# Sheet2.net
KiCad netlist of a schematic drawn in Altium Designer
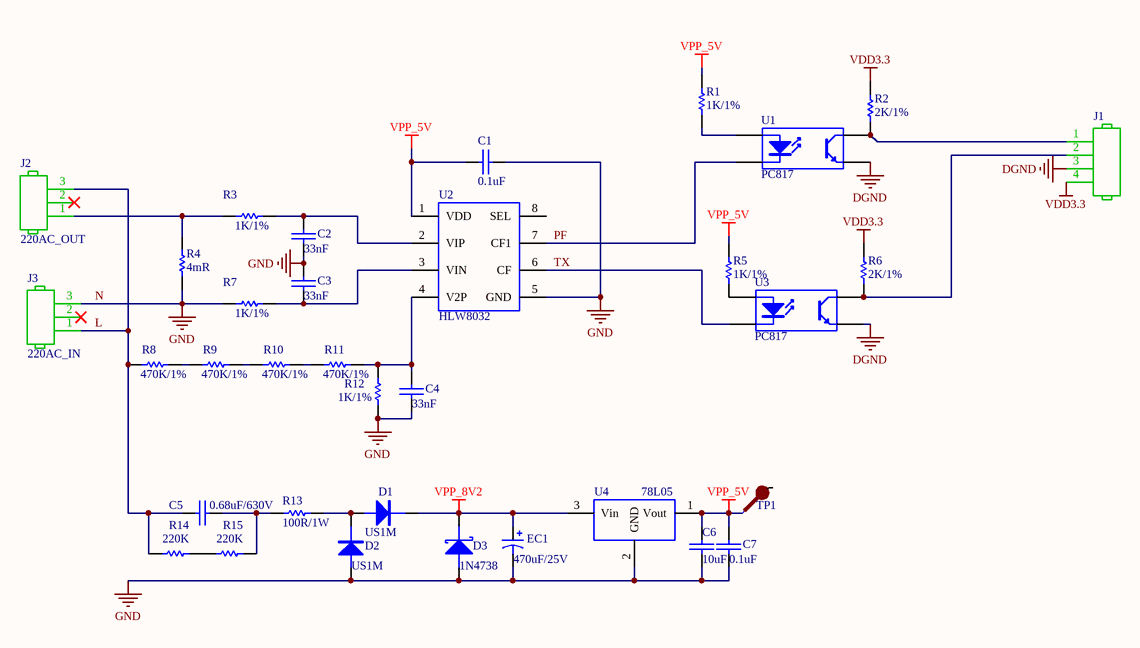
[diagram p0: Sheet2.SchDoc]

(export (version "E")
  (design (tool "Eeschema 10.0.6"))
  (components
    (comp (ref "C1")
      (value "0.1uF")
      (footprint "C0805")
      (description "33nF/50V/±10%/X7R")
      (libsource (lib "MYSchlib") (part "CAP"))
    )
    (comp (ref "C2")
      (value "33nF")
      (footprint "C0805")
      (description "33nF/50V/±10%/X7R")
      (libsource (lib "MYSchlib") (part "CAP"))
    )
    (comp (ref "C3")
      (value "33nF")
      (footprint "C0805")
      (description "33nF/50V/±10%/X7R")
      (libsource (lib "MYSchlib") (part "CAP"))
    )
    (comp (ref "C4")
      (value "33nF")
      (footprint "C0805")
      (description "33nF/50V/±10%/X7R")
      (libsource (lib "MYSchlib") (part "CAP"))
    )
    (comp (ref "C5")
      (value "0.68uF/630V")
      (footprint "CBB-20-V")
      (description "0.68uF/630V/CBB电容/脚距20")
      (libsource (lib "MYSchlib") (part "CAP"))
    )
    (comp (ref "C6")
      (value "10uF")
      (footprint "C0805")
      (description "10uF/10V/±10%/X7R")
      (libsource (lib "AD-SchLibV0.1-20160831") (part "CAP"))
    )
    (comp (ref "C7")
      (value "0.1uF")
      (footprint "C0805")
      (description "0.1uF/50V/±10%/X7R")
      (libsource (lib "MYSchlib") (part "CAP"))
    )
    (comp (ref "D1") (value "US1M") (footprint "DO-214AC(SMA)") (libsource (lib "MYSchlib") (part "DIODE")))
    (comp (ref "D2") (value "US1M") (footprint "DO-214AC(SMA)") (libsource (lib "MYSchlib") (part "DIODE")))
    (comp (ref "D3")
      (value "1N4738")
      (footprint "DO-214AC(SMA)")
      (libsource (lib "MYSchlib") (part "DIODE-S"))
    )
    (comp (ref "EC1")
      (value "470uF/25V")
      (footprint "C-IP-D8")
      (description "470uF/25V/±20%/8*12")
      (libsource (lib "MYSchlib") (part "CAP3"))
    )
    (comp (ref "J1")
      (value "~")
      (footprint "J-XH2.54-4-IPV")
      (description "XH2.54_4PIN/直插立式")
      (libsource (lib "my") (part "Header4"))
    )
    (comp (ref "J2")
      (value "220AC_OUT")
      (footprint "J-VH3.96-3-IPV")
      (description "VH3.96-3PIN/2脚空置/直插立式")
      (libsource (lib "my") (part "Header3"))
    )
    (comp (ref "J3")
      (value "220AC_IN")
      (footprint "J-VH3.96-3-IPV")
      (description "VH3.96-3PIN/2脚空置/直插立式")
      (libsource (lib "my") (part "Header3"))
    )
    (comp (ref "R1")
      (value "1K/1%")
      (footprint "R0805")
      (description "1K/±5%/1/10W")
      (libsource (lib "MYSchlib") (part "RES1"))
    )
    (comp (ref "R2")
      (value "2K/1%")
      (footprint "R0805")
      (description "1K/±5%/1/10W")
      (libsource (lib "MYSchlib") (part "RES1"))
    )
    (comp (ref "R3")
      (value "1K/1%")
      (footprint "R0805")
      (description "1K/±5%/1/10W")
      (libsource (lib "MYSchlib") (part "RES1"))
    )
    (comp (ref "R4")
      (value "4mR")
      (footprint "R-2512")
      (description "220K/±5%/1/4W")
      (libsource (lib "MYSchlib") (part "RES1"))
    )
    (comp (ref "R5")
      (value "1K/1%")
      (footprint "R0805")
      (description "1K/±5%/1/10W")
      (libsource (lib "MYSchlib") (part "RES1"))
    )
    (comp (ref "R6")
      (value "2K/1%")
      (footprint "R0805")
      (description "1K/±5%/1/10W")
      (libsource (lib "MYSchlib") (part "RES1"))
    )
    (comp (ref "R7")
      (value "1K/1%")
      (footprint "R0805")
      (description "1K/±5%/1/10W")
      (libsource (lib "MYSchlib") (part "RES1"))
    )
    (comp (ref "R8")
      (value "470K/1%")
      (footprint "R0805")
      (description "1K/±5%/1/10W")
      (libsource (lib "MYSchlib") (part "RES1"))
    )
    (comp (ref "R9")
      (value "470K/1%")
      (footprint "R0805")
      (description "1K/±5%/1/10W")
      (libsource (lib "MYSchlib") (part "RES1"))
    )
    (comp (ref "R10")
      (value "470K/1%")
      (footprint "R0805")
      (description "1K/±5%/1/10W")
      (libsource (lib "MYSchlib") (part "RES1"))
    )
    (comp (ref "R11")
      (value "470K/1%")
      (footprint "R0805")
      (description "1K/±5%/1/10W")
      (libsource (lib "MYSchlib") (part "RES1"))
    )
    (comp (ref "R12")
      (value "1K/1%")
      (footprint "R0805")
      (description "1K/±5%/1/10W")
      (libsource (lib "MYSchlib") (part "RES1"))
    )
    (comp (ref "R13")
      (value "100R/1W")
      (footprint "R-2512")
      (description "100R/±5%/1W/绕线电阻")
      (libsource (lib "MYSchlib") (part "RES1"))
    )
    (comp (ref "R14")
      (value "220K")
      (footprint "R-1206")
      (description "220K/±5%/1/4W")
      (libsource (lib "MYSchlib") (part "RES1"))
    )
    (comp (ref "R15")
      (value "220K")
      (footprint "R-1206")
      (description "220K/±5%/1/4W")
      (libsource (lib "MYSchlib") (part "RES1"))
    )
    (comp (ref "TP1") (value "TEST POINT") (footprint "TP-D2") (libsource (lib "MYSchlib") (part "TEST")))
    (comp (ref "U1")
      (value "PC817")
      (footprint "SOP4-2.54-6.5")
      (description "PC817C")
      (libsource (lib "MYSchlib") (part "PC817"))
    )
    (comp (ref "U2")
      (value "HLW8032")
      (footprint "SOP8-1.27-3.9")
      (description "HLW8012")
      (libsource (lib "MYSchlib") (part "HLW8012"))
    )
    (comp (ref "U3")
      (value "PC817")
      (footprint "SOP4-2.54-6.5")
      (description "PC817C")
      (libsource (lib "MYSchlib") (part "PC817"))
    )
    (comp (ref "U4")
      (value "78L05")
      (footprint "SOT89")
      (description "L78L05ACUTR")
      (libsource (lib "MYSchlib") (part "Voltage"))
    )
  )
  (nets
    (net (code "1") (name "/L") (class "Default")
      (node (ref "C5") (pin "2") (pinfunction "2_2") (pintype "passive"))
      (node (ref "J2") (pin "3") (pinfunction "3_3") (pintype "passive"))
      (node (ref "J3") (pin "1") (pinfunction "1_1") (pintype "passive"))
      (node (ref "R14") (pin "2") (pinfunction "2_2") (pintype "passive"))
      (node (ref "R8") (pin "1") (pinfunction "1_1") (pintype "passive"))
    )
    (net (code "2") (name "/PF") (class "Default")
      (node (ref "U1") (pin "2") (pinfunction "K_2") (pintype "passive"))
      (node (ref "U2") (pin "7") (pinfunction "CF1_7") (pintype "passive"))
    )
    (net (code "3") (name "/TX") (class "Default")
      (node (ref "U2") (pin "6") (pinfunction "CF_6") (pintype "passive"))
      (node (ref "U3") (pin "2") (pinfunction "K_2") (pintype "passive"))
    )
    (net (code "4") (name "DGND") (class "Default")
      (node (ref "J1") (pin "3") (pinfunction "3_3") (pintype "passive"))
      (node (ref "U1") (pin "3") (pinfunction "E_3") (pintype "passive"))
      (node (ref "U3") (pin "3") (pinfunction "E_3") (pintype "passive"))
    )
    (net (code "5") (name "GND") (class "Default")
      (node (ref "C1") (pin "2") (pinfunction "2_2") (pintype "passive"))
      (node (ref "C2") (pin "2") (pinfunction "2_2") (pintype "passive"))
      (node (ref "C3") (pin "1") (pinfunction "1_1") (pintype "passive"))
      (node (ref "C4") (pin "2") (pinfunction "2_2") (pintype "passive"))
      (node (ref "C6") (pin "1") (pinfunction "1_1") (pintype "passive"))
      (node (ref "C7") (pin "2") (pinfunction "2_2") (pintype "passive"))
      (node (ref "D2") (pin "1") (pinfunction "A_1") (pintype "passive"))
      (node (ref "D3") (pin "1") (pinfunction "A_1") (pintype "passive"))
      (node (ref "EC1") (pin "2") (pinfunction "2_2") (pintype "passive"))
      (node (ref "J3") (pin "3") (pinfunction "3_3") (pintype "passive"))
      (node (ref "R12") (pin "2") (pinfunction "2_2") (pintype "passive"))
      (node (ref "R4") (pin "2") (pinfunction "2_2") (pintype "passive"))
      (node (ref "R7") (pin "1") (pinfunction "1_1") (pintype "passive"))
      (node (ref "U2") (pin "5") (pinfunction "GND_5") (pintype "passive"))
      (node (ref "U4") (pin "2") (pinfunction "GND_2") (pintype "passive"))
    )
    (net (code "6") (name "Net-(C5-Pad1)") (class "Default")
      (node (ref "C5") (pin "1") (pinfunction "1_1") (pintype "passive"))
      (node (ref "R13") (pin "2") (pinfunction "2_2") (pintype "passive"))
      (node (ref "R15") (pin "1") (pinfunction "1_1") (pintype "passive"))
    )
    (net (code "7") (name "Net-(D1-A)") (class "Default")
      (node (ref "D1") (pin "1") (pinfunction "A_1") (pintype "passive"))
      (node (ref "D2") (pin "2") (pinfunction "K_2") (pintype "passive"))
      (node (ref "R13") (pin "1") (pinfunction "1_1") (pintype "passive"))
    )
    (net (code "8") (name "Net-(J2-Pad1)") (class "Default")
      (node (ref "J2") (pin "1") (pinfunction "1_1") (pintype "passive"))
      (node (ref "R3") (pin "1") (pinfunction "1_1") (pintype "passive"))
      (node (ref "R4") (pin "1") (pinfunction "1_1") (pintype "passive"))
    )
    (net (code "9") (name "Net-(R8-Pad2)") (class "Default")
      (node (ref "R8") (pin "2") (pinfunction "2_2") (pintype "passive"))
      (node (ref "R9") (pin "1") (pinfunction "1_1") (pintype "passive"))
    )
    (net (code "10") (name "Net-(R10-Pad1)") (class "Default")
      (node (ref "R10") (pin "1") (pinfunction "1_1") (pintype "passive"))
      (node (ref "R9") (pin "2") (pinfunction "2_2") (pintype "passive"))
    )
    (net (code "11") (name "Net-(R10-Pad2)") (class "Default")
      (node (ref "R10") (pin "2") (pinfunction "2_2") (pintype "passive"))
      (node (ref "R11") (pin "1") (pinfunction "1_1") (pintype "passive"))
    )
    (net (code "12") (name "Net-(R14-Pad1)") (class "Default")
      (node (ref "R14") (pin "1") (pinfunction "1_1") (pintype "passive"))
      (node (ref "R15") (pin "2") (pinfunction "2_2") (pintype "passive"))
    )
    (net (code "13") (name "Net-(U1-A)") (class "Default")
      (node (ref "R1") (pin "1") (pinfunction "1_1") (pintype "passive"))
      (node (ref "U1") (pin "1") (pinfunction "A_1") (pintype "passive"))
    )
    (net (code "14") (name "Net-(U1-C)") (class "Default")
      (node (ref "J1") (pin "1") (pinfunction "1_1") (pintype "passive"))
      (node (ref "R2") (pin "1") (pinfunction "1_1") (pintype "passive"))
      (node (ref "U1") (pin "4") (pinfunction "C_4") (pintype "passive"))
    )
    (net (code "15") (name "Net-(U2-V2P)") (class "Default")
      (node (ref "C4") (pin "1") (pinfunction "1_1") (pintype "passive"))
      (node (ref "R11") (pin "2") (pinfunction "2_2") (pintype "passive"))
      (node (ref "R12") (pin "1") (pinfunction "1_1") (pintype "passive"))
      (node (ref "U2") (pin "4") (pinfunction "V2P_4") (pintype "passive"))
    )
    (net (code "16") (name "Net-(U2-VIN)") (class "Default")
      (node (ref "C3") (pin "2") (pinfunction "2_2") (pintype "passive"))
      (node (ref "R7") (pin "2") (pinfunction "2_2") (pintype "passive"))
      (node (ref "U2") (pin "3") (pinfunction "VIN_3") (pintype "passive"))
    )
    (net (code "17") (name "Net-(U2-VIP)") (class "Default")
      (node (ref "C2") (pin "1") (pinfunction "1_1") (pintype "passive"))
      (node (ref "R3") (pin "2") (pinfunction "2_2") (pintype "passive"))
      (node (ref "U2") (pin "2") (pinfunction "VIP_2") (pintype "passive"))
    )
    (net (code "18") (name "Net-(U3-A)") (class "Default")
      (node (ref "R5") (pin "1") (pinfunction "1_1") (pintype "passive"))
      (node (ref "U3") (pin "1") (pinfunction "A_1") (pintype "passive"))
    )
    (net (code "19") (name "Net-(U3-C)") (class "Default")
      (node (ref "J1") (pin "2") (pinfunction "2_2") (pintype "passive"))
      (node (ref "R6") (pin "1") (pinfunction "1_1") (pintype "passive"))
      (node (ref "U3") (pin "4") (pinfunction "C_4") (pintype "passive"))
    )
    (net (code "20") (name "VDD3.3") (class "Default")
      (node (ref "J1") (pin "4") (pinfunction "4_4") (pintype "passive"))
      (node (ref "R2") (pin "2") (pinfunction "2_2") (pintype "passive"))
      (node (ref "R6") (pin "2") (pinfunction "2_2") (pintype "passive"))
    )
    (net (code "21") (name "VPP_5V") (class "Default")
      (node (ref "C1") (pin "1") (pinfunction "1_1") (pintype "passive"))
      (node (ref "C6") (pin "2") (pinfunction "2_2") (pintype "passive"))
      (node (ref "C7") (pin "1") (pinfunction "1_1") (pintype "passive"))
      (node (ref "R1") (pin "2") (pinfunction "2_2") (pintype "passive"))
      (node (ref "R5") (pin "2") (pinfunction "2_2") (pintype "passive"))
      (node (ref "TP1") (pin "1") (pinfunction "TEST_1") (pintype "passive"))
      (node (ref "U2") (pin "1") (pinfunction "VDD_1") (pintype "passive"))
      (node (ref "U4") (pin "1") (pinfunction "Vout_1") (pintype "passive"))
    )
    (net (code "22") (name "VPP_8V2") (class "Default")
      (node (ref "D1") (pin "2") (pinfunction "K_2") (pintype "passive"))
      (node (ref "D3") (pin "2") (pinfunction "K_2") (pintype "passive"))
      (node (ref "EC1") (pin "1") (pinfunction "1_1") (pintype "passive"))
      (node (ref "U4") (pin "3") (pinfunction "Vin_3") (pintype "passive"))
    )
    (net (code "23") (name "unconnected-(J2-Pad2)") (class "Default")
      (node (ref "J2") (pin "2") (pinfunction "2_2") (pintype "passive+no_connect"))
    )
    (net (code "24") (name "unconnected-(J3-Pad2)") (class "Default")
      (node (ref "J3") (pin "2") (pinfunction "2_2") (pintype "passive+no_connect"))
    )
    (net (code "25") (name "unconnected-(U2-SEL-Pad8)") (class "Default")
      (node (ref "U2") (pin "8") (pinfunction "SEL_8") (pintype "passive"))
    )
  )
)
